# Modem.net
KiCad netlist of a schematic drawn in Altium Designer
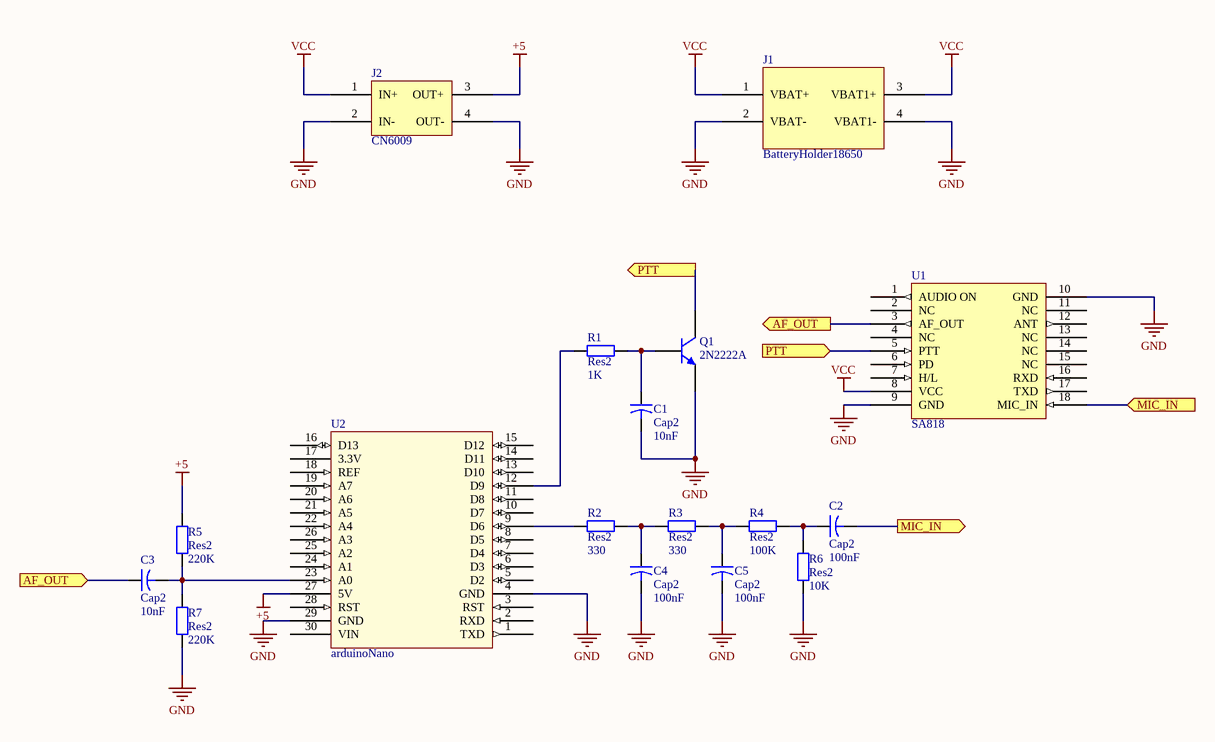
[diagram p0: Modem.SchDoc]

(export (version "E")
  (design (tool "Eeschema 10.0.6"))
  (components
    (comp (ref "C1")
      (value "Cap2")
      (footprint "CAPR5-4X5")
      (description "Capacitor")
      (fields (field (name "ALTIUM_VALUE") "10nF") (field (name "PUBLISHER") "Altium Limited"))
      (libsource (lib "Miscellaneous Devices") (part "Cap2"))
    )
    (comp (ref "C2")
      (value "Cap2")
      (footprint "CAPR5-4X5")
      (description "Capacitor")
      (fields (field (name "ALTIUM_VALUE") "100nF") (field (name "PUBLISHER") "Altium Limited"))
      (libsource (lib "Miscellaneous Devices") (part "Cap2"))
    )
    (comp (ref "C3")
      (value "Cap2")
      (footprint "CAPR5-4X5")
      (description "Capacitor")
      (fields (field (name "ALTIUM_VALUE") "10nF") (field (name "PUBLISHER") "Altium Limited"))
      (libsource (lib "Miscellaneous Devices") (part "Cap2"))
    )
    (comp (ref "C4")
      (value "Cap2")
      (footprint "CAPR5-4X5")
      (description "Capacitor")
      (fields (field (name "ALTIUM_VALUE") "100nF") (field (name "PUBLISHER") "Altium Limited"))
      (libsource (lib "Miscellaneous Devices") (part "Cap2"))
    )
    (comp (ref "C5")
      (value "Cap2")
      (footprint "CAPR5-4X5")
      (description "Capacitor")
      (fields (field (name "ALTIUM_VALUE") "100nF") (field (name "PUBLISHER") "Altium Limited"))
      (libsource (lib "Miscellaneous Devices") (part "Cap2"))
    )
    (comp (ref "J1")
      (value "BatteryHolder18650")
      (footprint "BatteryHolder18650")
      (libsource (lib "BatteryHolder18650") (part "BatteryHolder18650"))
    )
    (comp (ref "J2")
      (value "CN6009")
      (footprint "CN6009")
      (libsource (lib "BoostConverterModules") (part "CN6009"))
    )
    (comp (ref "Q1")
      (value "2N2222A")
      (footprint "TO-18")
      (description "High Speed Switches")
      (fields (field (name "PUBLISHER") "Altium Limited"))
      (libsource (lib "ST Discrete BJT") (part "2N2222A"))
    )
    (comp (ref "R1")
      (value "Res2")
      (footprint "AXIAL-0.4")
      (description "Resistor")
      (fields (field (name "ALTIUM_VALUE") "1K") (field (name "PUBLISHER") "Altium Limited"))
      (libsource (lib "") (part "Res2_1"))
    )
    (comp (ref "R2")
      (value "Res2")
      (footprint "AXIAL-0.4")
      (description "Resistor")
      (fields (field (name "ALTIUM_VALUE") "330") (field (name "PUBLISHER") "Altium Limited"))
      (libsource (lib "") (part "Res2_1"))
    )
    (comp (ref "R3")
      (value "Res2")
      (footprint "AXIAL-0.4")
      (description "Resistor")
      (fields (field (name "ALTIUM_VALUE") "330") (field (name "PUBLISHER") "Altium Limited"))
      (libsource (lib "") (part "Res2_1"))
    )
    (comp (ref "R4")
      (value "Res2")
      (footprint "AXIAL-0.4")
      (description "Resistor")
      (fields (field (name "ALTIUM_VALUE") "100K") (field (name "PUBLISHER") "Altium Limited"))
      (libsource (lib "") (part "Res2_1"))
    )
    (comp (ref "R5")
      (value "Res2")
      (footprint "AXIAL-0.4")
      (description "Resistor")
      (fields (field (name "ALTIUM_VALUE") "220K") (field (name "PUBLISHER") "Altium Limited"))
      (libsource (lib "Miscellaneous Devices") (part "Res2"))
    )
    (comp (ref "R6")
      (value "Res2")
      (footprint "AXIAL-0.4")
      (description "Resistor")
      (fields (field (name "ALTIUM_VALUE") "10K") (field (name "PUBLISHER") "Altium Limited"))
      (libsource (lib "Miscellaneous Devices") (part "Res2"))
    )
    (comp (ref "R7")
      (value "Res2")
      (footprint "AXIAL-0.4")
      (description "Resistor")
      (fields (field (name "ALTIUM_VALUE") "220K") (field (name "PUBLISHER") "Altium Limited"))
      (libsource (lib "Miscellaneous Devices") (part "Res2"))
    )
    (comp (ref "U1") (value "SA818") (footprint "SA818") (libsource (lib "SA818") (part "SA818")))
    (comp (ref "U2")
      (value "arduinoNano")
      (footprint "Arduino nano")
      (libsource (lib "arduinoNano") (part "arduinoNano"))
    )
  )
  (nets
    (net (code "1") (name "+5") (class "Default")
      (node (ref "J2") (pin "3") (pinfunction "OUT+_3") (pintype "power_in"))
      (node (ref "R5") (pin "2") (pinfunction "2_2") (pintype "passive"))
      (node (ref "U2") (pin "27") (pinfunction "5V_27") (pintype "power_in"))
    )
    (net (code "2") (name "/AF_OUT") (class "Default")
      (node (ref "C3") (pin "1") (pinfunction "1_1") (pintype "passive"))
      (node (ref "U1") (pin "3") (pinfunction "AF_OUT_3") (pintype "output"))
    )
    (net (code "3") (name "/MIC_IN") (class "Default")
      (node (ref "C2") (pin "2") (pinfunction "2_2") (pintype "passive"))
      (node (ref "U1") (pin "18") (pinfunction "MIC_IN_18") (pintype "input"))
    )
    (net (code "4") (name "/PTT") (class "Default")
      (node (ref "Q1") (pin "2") (pinfunction "C_2") (pintype "passive"))
      (node (ref "U1") (pin "5") (pinfunction "PTT_5") (pintype "input"))
    )
    (net (code "5") (name "GND") (class "Default")
      (node (ref "C1") (pin "2") (pinfunction "2_2") (pintype "passive"))
      (node (ref "C4") (pin "2") (pinfunction "2_2") (pintype "passive"))
      (node (ref "C5") (pin "2") (pinfunction "2_2") (pintype "passive"))
      (node (ref "J1") (pin "2") (pinfunction "VBAT-_2") (pintype "passive"))
      (node (ref "J1") (pin "4") (pinfunction "VBAT1-_4") (pintype "passive"))
      (node (ref "J2") (pin "2") (pinfunction "IN-_2") (pintype "power_in"))
      (node (ref "J2") (pin "4") (pinfunction "OUT-_4") (pintype "power_in"))
      (node (ref "Q1") (pin "3") (pinfunction "E_3") (pintype "passive"))
      (node (ref "R6") (pin "1") (pinfunction "1_1") (pintype "passive"))
      (node (ref "R7") (pin "1") (pinfunction "1_1") (pintype "passive"))
      (node (ref "U1") (pin "10") (pinfunction "GND_10") (pintype "power_in"))
      (node (ref "U1") (pin "9") (pinfunction "GND_9") (pintype "power_in"))
      (node (ref "U2") (pin "29") (pinfunction "GND_29") (pintype "power_in"))
      (node (ref "U2") (pin "4") (pinfunction "GND_4") (pintype "power_in"))
    )
    (net (code "6") (name "Net-(C2-Pad1)") (class "Default")
      (node (ref "C2") (pin "1") (pinfunction "1_1") (pintype "passive"))
      (node (ref "R4") (pin "2") (pinfunction "2_2") (pintype "passive"))
      (node (ref "R6") (pin "2") (pinfunction "2_2") (pintype "passive"))
    )
    (net (code "7") (name "Net-(C4-Pad1)") (class "Default")
      (node (ref "C4") (pin "1") (pinfunction "1_1") (pintype "passive"))
      (node (ref "R2") (pin "2") (pinfunction "2_2") (pintype "passive"))
      (node (ref "R3") (pin "1") (pinfunction "1_1") (pintype "passive"))
    )
    (net (code "8") (name "Net-(C5-Pad1)") (class "Default")
      (node (ref "C5") (pin "1") (pinfunction "1_1") (pintype "passive"))
      (node (ref "R3") (pin "2") (pinfunction "2_2") (pintype "passive"))
      (node (ref "R4") (pin "1") (pinfunction "1_1") (pintype "passive"))
    )
    (net (code "9") (name "Net-(Q1-B)") (class "Default")
      (node (ref "C1") (pin "1") (pinfunction "1_1") (pintype "passive"))
      (node (ref "Q1") (pin "1") (pinfunction "B_1") (pintype "passive"))
      (node (ref "R1") (pin "2") (pinfunction "2_2") (pintype "passive"))
    )
    (net (code "10") (name "Net-(U2-A0)") (class "Default")
      (node (ref "C3") (pin "2") (pinfunction "2_2") (pintype "passive"))
      (node (ref "R5") (pin "1") (pinfunction "1_1") (pintype "passive"))
      (node (ref "R7") (pin "2") (pinfunction "2_2") (pintype "passive"))
      (node (ref "U2") (pin "23") (pinfunction "A0_23") (pintype "input"))
    )
    (net (code "11") (name "Net-(U2-D6)") (class "Default")
      (node (ref "R2") (pin "1") (pinfunction "1_1") (pintype "passive"))
      (node (ref "U2") (pin "9") (pinfunction "D6_9") (pintype "bidirectional"))
    )
    (net (code "12") (name "Net-(U2-D9)") (class "Default")
      (node (ref "R1") (pin "1") (pinfunction "1_1") (pintype "passive"))
      (node (ref "U2") (pin "12") (pinfunction "D9_12") (pintype "bidirectional"))
    )
    (net (code "13") (name "VCC") (class "Default")
      (node (ref "J1") (pin "1") (pinfunction "VBAT+_1") (pintype "passive"))
      (node (ref "J1") (pin "3") (pinfunction "VBAT1+_3") (pintype "passive"))
      (node (ref "J2") (pin "1") (pinfunction "IN+_1") (pintype "power_in"))
      (node (ref "U1") (pin "8") (pinfunction "VCC_8") (pintype "power_in"))
    )
    (net (code "14") (name "unconnected-(U1-ANT-Pad12)") (class "Default")
      (node (ref "U1") (pin "12") (pinfunction "ANT_12") (pintype "output"))
    )
    (net (code "15") (name "unconnected-(U1-AUDIO_ON-Pad1)") (class "Default")
      (node (ref "U1") (pin "1") (pinfunction "AUDIO_ON_1") (pintype "output"))
    )
    (net (code "16") (name "unconnected-(U1-H{slash}L-Pad7)") (class "Default")
      (node (ref "U1") (pin "7") (pinfunction "H/L_7") (pintype "input"))
    )
    (net (code "17") (name "unconnected-(U1-NC-Pad2)") (class "Default")
      (node (ref "U1") (pin "2") (pinfunction "NC_2") (pintype "passive"))
    )
    (net (code "18") (name "unconnected-(U1-NC-Pad4)") (class "Default")
      (node (ref "U1") (pin "4") (pinfunction "NC_4") (pintype "passive"))
    )
    (net (code "19") (name "unconnected-(U1-NC-Pad11)") (class "Default")
      (node (ref "U1") (pin "11") (pinfunction "NC_11") (pintype "passive"))
    )
    (net (code "20") (name "unconnected-(U1-NC-Pad13)") (class "Default")
      (node (ref "U1") (pin "13") (pinfunction "NC_13") (pintype "passive"))
    )
    (net (code "21") (name "unconnected-(U1-NC-Pad14)") (class "Default")
      (node (ref "U1") (pin "14") (pinfunction "NC_14") (pintype "passive"))
    )
    (net (code "22") (name "unconnected-(U1-NC-Pad15)") (class "Default")
      (node (ref "U1") (pin "15") (pinfunction "NC_15") (pintype "passive"))
    )
    (net (code "23") (name "unconnected-(U1-PD-Pad6)") (class "Default")
      (node (ref "U1") (pin "6") (pinfunction "PD_6") (pintype "input"))
    )
    (net (code "24") (name "unconnected-(U1-RXD-Pad16)") (class "Default")
      (node (ref "U1") (pin "16") (pinfunction "RXD_16") (pintype "input"))
    )
    (net (code "25") (name "unconnected-(U1-TXD-Pad17)") (class "Default")
      (node (ref "U1") (pin "17") (pinfunction "TXD_17") (pintype "output"))
    )
    (net (code "26") (name "unconnected-(U2-3.3V-Pad17)") (class "Default")
      (node (ref "U2") (pin "17") (pinfunction "3.3V_17") (pintype "power_in"))
    )
    (net (code "27") (name "unconnected-(U2-A1-Pad24)") (class "Default")
      (node (ref "U2") (pin "24") (pinfunction "A1_24") (pintype "input"))
    )
    (net (code "28") (name "unconnected-(U2-A2-Pad25)") (class "Default")
      (node (ref "U2") (pin "25") (pinfunction "A2_25") (pintype "input"))
    )
    (net (code "29") (name "unconnected-(U2-A3-Pad26)") (class "Default")
      (node (ref "U2") (pin "26") (pinfunction "A3_26") (pintype "input"))
    )
    (net (code "30") (name "unconnected-(U2-A4-Pad22)") (class "Default")
      (node (ref "U2") (pin "22") (pinfunction "A4_22") (pintype "input"))
    )
    (net (code "31") (name "unconnected-(U2-A5-Pad21)") (class "Default")
      (node (ref "U2") (pin "21") (pinfunction "A5_21") (pintype "input"))
    )
    (net (code "32") (name "unconnected-(U2-A6-Pad20)") (class "Default")
      (node (ref "U2") (pin "20") (pinfunction "A6_20") (pintype "input"))
    )
    (net (code "33") (name "unconnected-(U2-A7-Pad19)") (class "Default")
      (node (ref "U2") (pin "19") (pinfunction "A7_19") (pintype "input"))
    )
    (net (code "34") (name "unconnected-(U2-D2-Pad5)") (class "Default")
      (node (ref "U2") (pin "5") (pinfunction "D2_5") (pintype "bidirectional"))
    )
    (net (code "35") (name "unconnected-(U2-D3-Pad6)") (class "Default")
      (node (ref "U2") (pin "6") (pinfunction "D3_6") (pintype "bidirectional"))
    )
    (net (code "36") (name "unconnected-(U2-D4-Pad7)") (class "Default")
      (node (ref "U2") (pin "7") (pinfunction "D4_7") (pintype "bidirectional"))
    )
    (net (code "37") (name "unconnected-(U2-D5-Pad8)") (class "Default")
      (node (ref "U2") (pin "8") (pinfunction "D5_8") (pintype "bidirectional"))
    )
    (net (code "38") (name "unconnected-(U2-D7-Pad10)") (class "Default")
      (node (ref "U2") (pin "10") (pinfunction "D7_10") (pintype "bidirectional"))
    )
    (net (code "39") (name "unconnected-(U2-D8-Pad11)") (class "Default")
      (node (ref "U2") (pin "11") (pinfunction "D8_11") (pintype "bidirectional"))
    )
    (net (code "40") (name "unconnected-(U2-D10-Pad13)") (class "Default")
      (node (ref "U2") (pin "13") (pinfunction "D10_13") (pintype "bidirectional"))
    )
    (net (code "41") (name "unconnected-(U2-D11-Pad14)") (class "Default")
      (node (ref "U2") (pin "14") (pinfunction "D11_14") (pintype "bidirectional"))
    )
    (net (code "42") (name "unconnected-(U2-D12-Pad15)") (class "Default")
      (node (ref "U2") (pin "15") (pinfunction "D12_15") (pintype "bidirectional"))
    )
    (net (code "43") (name "unconnected-(U2-D13-Pad16)") (class "Default")
      (node (ref "U2") (pin "16") (pinfunction "D13_16") (pintype "bidirectional"))
    )
    (net (code "44") (name "unconnected-(U2-REF-Pad18)") (class "Default")
      (node (ref "U2") (pin "18") (pinfunction "REF_18") (pintype "input"))
    )
    (net (code "45") (name "unconnected-(U2-RST-Pad3)") (class "Default")
      (node (ref "U2") (pin "3") (pinfunction "RST_3") (pintype "input"))
    )
    (net (code "46") (name "unconnected-(U2-RST-Pad28)") (class "Default")
      (node (ref "U2") (pin "28") (pinfunction "RST_28") (pintype "input"))
    )
    (net (code "47") (name "unconnected-(U2-RXD-Pad2)") (class "Default")
      (node (ref "U2") (pin "2") (pinfunction "RXD_2") (pintype "input"))
    )
    (net (code "48") (name "unconnected-(U2-TXD-Pad1)") (class "Default")
      (node (ref "U2") (pin "1") (pinfunction "TXD_1") (pintype "output"))
    )
    (net (code "49") (name "unconnected-(U2-VIN-Pad30)") (class "Default")
      (node (ref "U2") (pin "30") (pinfunction "VIN_30") (pintype "power_in"))
    )
  )
)
